# Schematic_page1.net
KiCad netlist of a schematic drawn in Altium Designer
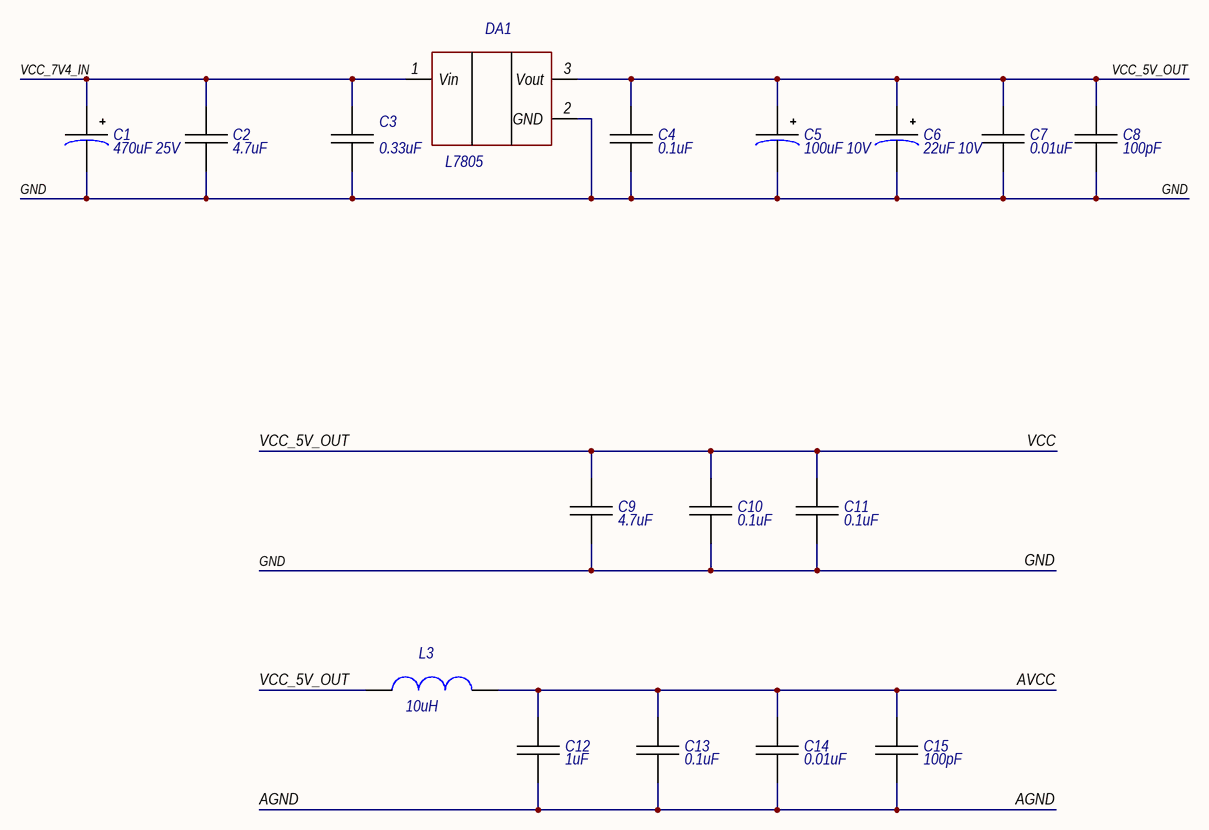
[diagram p0: Schematic_page1.SchDoc]

(export (version "E")
  (design (tool "Eeschema 10.0.6"))
  (components
    (comp (ref "C1")
      (value "470uF 25V")
      (footprint "CapElec_8x16_3.5mm")
      (fields (field (name "MANUFACTURER") "JB"))
      (libsource (lib "Board_lib") (part "Capacitor_Elec"))
    )
    (comp (ref "C2") (value "4.7uF") (footprint "C0603") (libsource (lib "Board_lib") (part "Capasitor")))
    (comp (ref "C3") (value "0.33uF") (footprint "C0603") (libsource (lib "Board_lib") (part "Capasitor")))
    (comp (ref "C4") (value "0.1uF") (footprint "C0603") (libsource (lib "Board_lib") (part "Capasitor")))
    (comp (ref "C5")
      (value "100uF 10V")
      (footprint "CapElec_5x11_2mm")
      (fields (field (name "MANUFACTURER") "JB"))
      (libsource (lib "Board_lib") (part "Capacitor_Elec"))
    )
    (comp (ref "C6")
      (value "22uF 10V")
      (footprint "TANT-B")
      (libsource (lib "Board_lib") (part "Capasitor_Tantalum"))
    )
    (comp (ref "C7") (value "0.01uF") (footprint "C0603") (libsource (lib "Board_lib") (part "Capasitor")))
    (comp (ref "C8") (value "100pF") (footprint "C0603") (libsource (lib "Board_lib") (part "Capasitor")))
    (comp (ref "C9") (value "4.7uF") (footprint "C0603") (libsource (lib "Board_lib") (part "Capasitor")))
    (comp (ref "C10") (value "0.1uF") (footprint "C0603") (libsource (lib "Board_lib") (part "Capasitor")))
    (comp (ref "C11") (value "0.1uF") (footprint "C0603") (libsource (lib "Board_lib") (part "Capasitor")))
    (comp (ref "C12") (value "1uF") (footprint "C0603") (libsource (lib "Board_lib") (part "Capasitor")))
    (comp (ref "C13") (value "0.1uF") (footprint "C0603") (libsource (lib "Board_lib") (part "Capasitor")))
    (comp (ref "C14") (value "0.01uF") (footprint "C0603") (libsource (lib "Board_lib") (part "Capasitor")))
    (comp (ref "C15") (value "100pF") (footprint "C0603") (libsource (lib "Board_lib") (part "Capasitor")))
    (comp (ref "DA1")
      (value "L7805")
      (footprint "TO-220A")
      (description "Linear Voltage Regulator IC  1 Output  1.5A TO-220AB")
      (fields (field (name "MANUFACTURER") "STMicroelectronics"))
      (libsource (lib "Board_lib") (part "L75xx"))
    )
    (comp (ref "L3") (value "10uH") (footprint "IND1206") (libsource (lib "Board_lib") (part "Inductivity")))
  )
  (nets
    (net (code "1") (name "/AGND") (class "Default")
      (node (ref "C12") (pin "2") (pintype "passive"))
      (node (ref "C13") (pin "2") (pintype "passive"))
      (node (ref "C14") (pin "2") (pintype "passive"))
      (node (ref "C15") (pin "2") (pintype "passive"))
    )
    (net (code "2") (name "/AVCC") (class "Default")
      (node (ref "C12") (pin "1") (pintype "passive"))
      (node (ref "C13") (pin "1") (pintype "passive"))
      (node (ref "C14") (pin "1") (pintype "passive"))
      (node (ref "C15") (pin "1") (pintype "passive"))
      (node (ref "L3") (pin "2") (pintype "passive"))
    )
    (net (code "3") (name "/GND") (class "Default")
      (node (ref "C1") (pin "2") (pintype "passive"))
      (node (ref "C10") (pin "2") (pintype "passive"))
      (node (ref "C11") (pin "2") (pintype "passive"))
      (node (ref "C2") (pin "2") (pintype "passive"))
      (node (ref "C3") (pin "2") (pintype "passive"))
      (node (ref "C4") (pin "2") (pintype "passive"))
      (node (ref "C5") (pin "2") (pintype "passive"))
      (node (ref "C6") (pin "2") (pintype "passive"))
      (node (ref "C7") (pin "2") (pintype "passive"))
      (node (ref "C8") (pin "2") (pintype "passive"))
      (node (ref "C9") (pin "2") (pintype "passive"))
      (node (ref "DA1") (pin "2") (pinfunction "GND_2") (pintype "passive"))
    )
    (net (code "4") (name "/VCC") (class "Default")
      (node (ref "C10") (pin "1") (pintype "passive"))
      (node (ref "C11") (pin "1") (pintype "passive"))
      (node (ref "C4") (pin "1") (pintype "passive"))
      (node (ref "C5") (pin "1") (pintype "passive"))
      (node (ref "C6") (pin "1") (pintype "passive"))
      (node (ref "C7") (pin "1") (pintype "passive"))
      (node (ref "C8") (pin "1") (pintype "passive"))
      (node (ref "C9") (pin "1") (pintype "passive"))
      (node (ref "DA1") (pin "3") (pinfunction "Vout_3") (pintype "passive"))
      (node (ref "L3") (pin "1") (pintype "passive"))
    )
    (net (code "5") (name "/VCC_7V4_IN") (class "Default")
      (node (ref "C1") (pin "1") (pintype "passive"))
      (node (ref "C2") (pin "1") (pintype "passive"))
      (node (ref "C3") (pin "1") (pintype "passive"))
      (node (ref "DA1") (pin "1") (pinfunction "Vin_1") (pintype "passive"))
    )
  )
)
